# Sheet1.net
KiCad netlist of a schematic drawn in Altium Designer
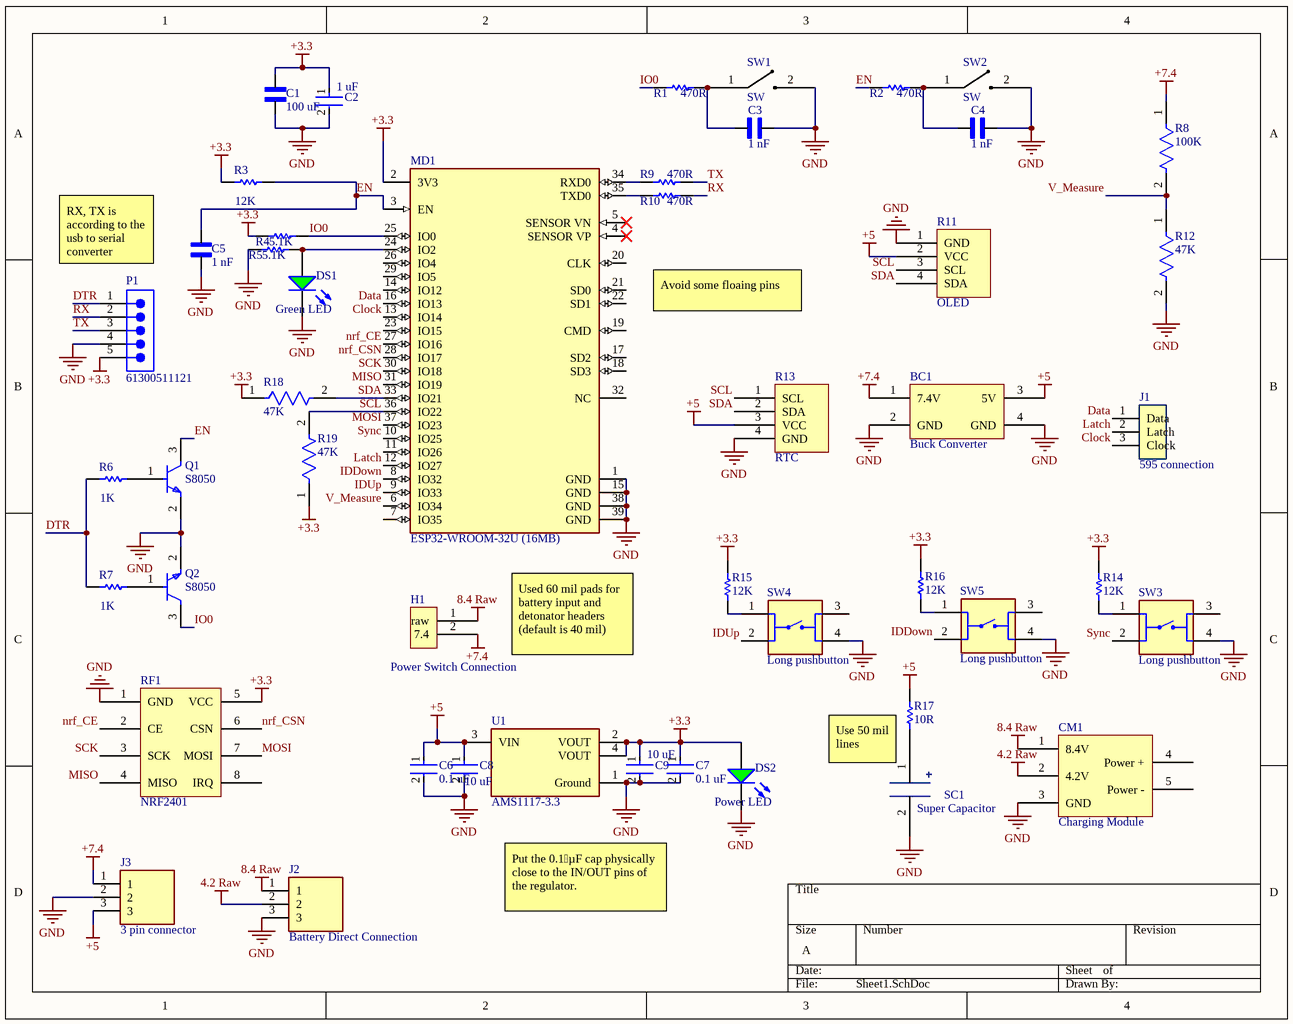
[diagram p0: Sheet1.SchDoc]

(export (version "E")
  (design (tool "Eeschema 10.0.6"))
  (components
    (comp (ref "BC1")
      (value "Buck Converter")
      (footprint "Buck Converter")
      (libsource (lib "Firework Detenator PCB") (part "Buck Converter"))
    )
    (comp (ref "C1")
      (value "100 uF")
      (footprint "0805 CAP")
      (description "10000 pF Â±5% 16V Ceramic Capacitor X7R 0805 (2012 Metric)")
      (fields (field (name "MF") "AVX") (field (name "MP") "0805YC103J4T2A"))
      (libsource (lib "Firework Detenator PCB") (part "0805 cap"))
    )
    (comp (ref "C2")
      (value "1 uF")
      (footprint "FP-CL21-IPC_A")
      (description "CL21 Series 0805 10uF 25V ±10% Tolerance X5R Multilayer Ceramic Chip Capacitor")
      (fields (field (name "TOLERANCE") "10%"))
      (libsource (lib "Altium Content Vault") (part "b4654b650e69147ec39a6b967a45e02"))
    )
    (comp (ref "C3")
      (value "1 nF")
      (footprint "0805 CAP")
      (description "10000 pF Â±5% 16V Ceramic Capacitor X7R 0805 (2012 Metric)")
      (fields (field (name "MF") "AVX") (field (name "MP") "0805YC103J4T2A"))
      (libsource (lib "") (part "0805 cap_1"))
    )
    (comp (ref "C4")
      (value "1 nF")
      (footprint "0805 CAP")
      (description "10000 pF Â±5% 16V Ceramic Capacitor X7R 0805 (2012 Metric)")
      (fields (field (name "MF") "AVX") (field (name "MP") "0805YC103J4T2A"))
      (libsource (lib "") (part "0805 cap_1"))
    )
    (comp (ref "C5")
      (value "1 nF")
      (footprint "0805 CAP")
      (description "10000 pF Â±5% 16V Ceramic Capacitor X7R 0805 (2012 Metric)")
      (fields (field (name "MF") "AVX") (field (name "MP") "0805YC103J4T2A"))
      (libsource (lib "Firework Detenator PCB") (part "0805 cap"))
    )
    (comp (ref "C6")
      (value "0.1 uF")
      (footprint "FP-CC0805-0_85-MFG")
      (description "CAP CER 0.1UF 50V X7R 0805")
      (fields (field (name "TOLERANCE") "0.1") (field (name "MANUFACTURER PART NUMBER") "CC0805KRX7R9BB104"))
      (libsource (lib "Altium Content Vault") (part "11868f565c42a9108669ba33697ecf6"))
    )
    (comp (ref "C7")
      (value "0.1 uF")
      (footprint "FP-CC0805-0_85-MFG")
      (description "CAP CER 0.1UF 50V X7R 0805")
      (fields (field (name "TOLERANCE") "0.1") (field (name "MANUFACTURER PART NUMBER") "CC0805KRX7R9BB104"))
      (libsource (lib "Altium Content Vault") (part "11868f565c42a9108669ba33697ecf6"))
    )
    (comp (ref "C8")
      (value "10 uF")
      (footprint "FP-CL21-IPC_A")
      (description "CL21 Series 0805 10uF 25V ±10% Tolerance X5R Multilayer Ceramic Chip Capacitor")
      (fields (field (name "TOLERANCE") "10%"))
      (libsource (lib "Altium Content Vault") (part "b4654b650e69147ec39a6b967a45e02"))
    )
    (comp (ref "C9")
      (value "10 uF")
      (footprint "FP-CL21-IPC_A")
      (description "CL21 Series 0805 10uF 25V ±10% Tolerance X5R Multilayer Ceramic Chip Capacitor")
      (fields (field (name "TOLERANCE") "10%"))
      (libsource (lib "Altium Content Vault") (part "b4654b650e69147ec39a6b967a45e02"))
    )
    (comp (ref "CM1")
      (value "Charging Module")
      (footprint "2S Charging Module")
      (libsource (lib "Firework Detenator PCB") (part "2S Charging module"))
    )
    (comp (ref "DS1")
      (value "Green LED")
      (footprint "DIAL-0805-2_V")
      (description "Single Color, 2 V, -30 to 85 degC, 2-Pin SMD (0805), RoHS, Tape and Reel")
      (fields (field (name "MANUFACTURER") "Dialight"))
      (libsource (lib "Altium Content Vault") (part "LED-GREEN-AK-2"))
    )
    (comp (ref "DS2")
      (value "Power LED")
      (footprint "DIAL-0805-2_V")
      (description "Single Color, 2 V, -30 to 85 degC, 2-Pin SMD (0805), RoHS, Tape and Reel")
      (fields (field (name "MANUFACTURER") "Dialight"))
      (libsource (lib "Altium Content Vault") (part "LED-GREEN-AK-2"))
    )
    (comp (ref "H1")
      (value "Power Switch Connection")
      (footprint "2 Pin Header L")
      (libsource (lib "Firework Detenator PCB") (part "2 pin header"))
    )
    (comp (ref "J1")
      (value "595 connection")
      (footprint "3 pin header")
      (description "3P,STRAIGHT,SIDE ENTRY,3.5MM")
      (fields (field (name "MF") "TE Connectivity") (field (name "MP") "1546551-3"))
      (libsource (lib "Firework Detenator PCB") (part "3 pin header"))
    )
    (comp (ref "J2")
      (value "Battery Direct Connection")
      (footprint "3 pin connector")
      (description "3P,STRAIGHT,SIDE ENTRY,3.5MM")
      (fields (field (name "MF") "TE Connectivity") (field (name "MP") "1546551-3"))
      (libsource (lib "Firework Detenator PCB") (part "3 pin connector"))
    )
    (comp (ref "J3")
      (value "3 pin connector")
      (footprint "3 pin connector")
      (description "3P,STRAIGHT,SIDE ENTRY,3.5MM")
      (fields (field (name "MF") "TE Connectivity") (field (name "MP") "1546551-3"))
      (libsource (lib "Firework Detenator PCB") (part "3 pin connector"))
    )
    (comp (ref "MD1")
      (value "ESP32-WROOM-32U (16MB)")
      (footprint "FP-ESP32-WROOM-32U_16MB-MFG")
      (description "RX TXRX MODULE WIFI U.FL SMD")
      (libsource (lib "Altium Content Vault") (part "9bfa6d67090bf770919afa182987e90"))
    )
    (comp (ref "P1")
      (value "61300511121")
      (footprint "61300511121")
      (libsource (lib "Altium Content Vault") (part "Header_Male_1R_05P"))
    )
    (comp (ref "Q1")
      (value "S8050")
      (footprint "FP-SOT23-IPC_A")
      (description "TRANS NPN 40V 0.2A SMD SOT23-3")
      (libsource (lib "Altium Content Vault") (part "b44e953556f554d0102664c7d152cb4"))
    )
    (comp (ref "Q2")
      (value "S8050")
      (footprint "FP-SOT23-IPC_A")
      (description "TRANS NPN 40V 0.2A SMD SOT23-3")
      (libsource (lib "Altium Content Vault") (part "b44e953556f554d0102664c7d152cb4"))
    )
    (comp (ref "R1")
      (value "470R")
      (footprint "RESC2013X50X30LL20T20")
      (fields (field (name "MANUFACTURER") "Vishay Dale") (field (name "PART NUMBER") "CRCW08050000Z0EA"))
      (libsource (lib "Altium Content Vault") (part "RES"))
    )
    (comp (ref "R2")
      (value "470R")
      (footprint "RESC2013X50X30LL20T20")
      (fields (field (name "MANUFACTURER") "Vishay Dale") (field (name "PART NUMBER") "CRCW08050000Z0EA"))
      (libsource (lib "Altium Content Vault") (part "RES"))
    )
    (comp (ref "R3")
      (value "12K")
      (footprint "RESC2013X50X30LL20T20")
      (fields (field (name "MANUFACTURER") "Vishay Dale") (field (name "PART NUMBER") "CRCW08050000Z0EA"))
      (libsource (lib "Altium Content Vault") (part "RES"))
    )
    (comp (ref "R4")
      (value "5.1K")
      (footprint "RESC2013X50X30LL20T20")
      (fields (field (name "MANUFACTURER") "Vishay Dale") (field (name "PART NUMBER") "CRCW08050000Z0EA"))
      (libsource (lib "Altium Content Vault") (part "RES"))
    )
    (comp (ref "R5")
      (value "5.1K")
      (footprint "RESC2013X50X30LL20T20")
      (fields (field (name "MANUFACTURER") "Vishay Dale") (field (name "PART NUMBER") "CRCW08050000Z0EA"))
      (libsource (lib "Altium Content Vault") (part "RES"))
    )
    (comp (ref "R6")
      (value "1K")
      (footprint "RESC2013X50X30LL20T20")
      (fields (field (name "MANUFACTURER") "Vishay Dale") (field (name "PART NUMBER") "CRCW08050000Z0EA"))
      (libsource (lib "Altium Content Vault") (part "RES"))
    )
    (comp (ref "R7")
      (value "1K")
      (footprint "RESC2013X50X30LL20T20")
      (fields (field (name "MANUFACTURER") "Vishay Dale") (field (name "PART NUMBER") "CRCW08050000Z0EA"))
      (libsource (lib "Altium Content Vault") (part "RES"))
    )
    (comp (ref "R8")
      (value "100K")
      (footprint "FP-RC0805-0_6-MFG")
      (description "RES SMD 100K OHM 5% 1/8W 0805")
      (fields (field (name "TOLERANCE") "5%"))
      (libsource (lib "Altium Content Vault") (part "8db39607336c341a927600551d01821"))
    )
    (comp (ref "R9")
      (value "470R")
      (footprint "RESC2013X50X30LL20T20")
      (fields (field (name "MANUFACTURER") "Vishay Dale") (field (name "PART NUMBER") "CRCW08050000Z0EA"))
      (libsource (lib "Altium Content Vault") (part "RES"))
    )
    (comp (ref "R10")
      (value "470R")
      (footprint "RESC2013X50X30LL20T20")
      (fields (field (name "MANUFACTURER") "Vishay Dale") (field (name "PART NUMBER") "CRCW08050000Z0EA"))
      (libsource (lib "Altium Content Vault") (part "RES"))
    )
    (comp (ref "R11")
      (value "OLED")
      (footprint "OLED")
      (libsource (lib "Firework Detenator PCB") (part "OLED"))
    )
    (comp (ref "R12")
      (value "47K")
      (footprint "FP-CRCW0805-e3-MFG")
      (description "RES Thick Film, 47kΩ, 1%, 0.125W, 100ppm/°C, 0805")
      (fields (field (name "TOLERANCE") "1%"))
      (libsource (lib "Altium Content Vault") (part "1029c3af85768c4190bb7ad29bc67b5"))
    )
    (comp (ref "R13") (value "RTC") (footprint "RTC") (libsource (lib "Firework Detenator PCB") (part "RTC")))
    (comp (ref "R14")
      (value "12K")
      (footprint "RESC2013X50X30LL20T20")
      (fields (field (name "MANUFACTURER") "Vishay Dale") (field (name "PART NUMBER") "CRCW08050000Z0EA"))
      (libsource (lib "Altium Content Vault") (part "RES"))
    )
    (comp (ref "R15")
      (value "12K")
      (footprint "RESC2013X50X30LL20T20")
      (fields (field (name "MANUFACTURER") "Vishay Dale") (field (name "PART NUMBER") "CRCW08050000Z0EA"))
      (libsource (lib "Altium Content Vault") (part "RES"))
    )
    (comp (ref "R16")
      (value "12K")
      (footprint "RESC2013X50X30LL20T20")
      (fields (field (name "MANUFACTURER") "Vishay Dale") (field (name "PART NUMBER") "CRCW08050000Z0EA"))
      (libsource (lib "Altium Content Vault") (part "RES"))
    )
    (comp (ref "R17")
      (value "10R")
      (footprint "RESC2013X50X30LL20T20")
      (fields (field (name "MANUFACTURER") "Vishay Dale") (field (name "PART NUMBER") "CRCW08050000Z0EA"))
      (libsource (lib "Altium Content Vault") (part "RES"))
    )
    (comp (ref "R18")
      (value "47K")
      (footprint "FP-CRCW0805-e3-MFG")
      (description "RES Thick Film, 47kΩ, 1%, 0.125W, 100ppm/°C, 0805")
      (fields (field (name "TOLERANCE") "1%"))
      (libsource (lib "Altium Content Vault") (part "1029c3af85768c4190bb7ad29bc67b5"))
    )
    (comp (ref "R19")
      (value "47K")
      (footprint "FP-CRCW0805-e3-MFG")
      (description "RES Thick Film, 47kΩ, 1%, 0.125W, 100ppm/°C, 0805")
      (fields (field (name "TOLERANCE") "1%"))
      (libsource (lib "Altium Content Vault") (part "1029c3af85768c4190bb7ad29bc67b5"))
    )
    (comp (ref "RF1")
      (value "NRF2401")
      (footprint "nrf2401")
      (libsource (lib "Firework Detenator PCB") (part "nrf2401"))
    )
    (comp (ref "SC1")
      (value "Super Capacitor")
      (footprint "Super Capacitor")
      (libsource (lib "Firework Detenator PCB") (part "Super Capacitor"))
    )
    (comp (ref "SW1")
      (value "SW")
      (footprint "smd push button 2")
      (libsource (lib "Firework Detenator PCB") (part "push button smd"))
    )
    (comp (ref "SW2")
      (value "SW")
      (footprint "smd push button 2")
      (libsource (lib "Firework Detenator PCB") (part "push button smd"))
    )
    (comp (ref "SW3")
      (value "Long pushbutton")
      (footprint "TH PB")
      (description "Switch Push Button OFF (ON) SPST Round Button 0.05A 24VDC Momentary Contact PC Pins Thru-Hole")
      (fields (field (name "MP") "1825910-6") (field (name "MF") "TE Connectivity"))
      (libsource (lib "Firework Detenator PCB") (part "TH PB"))
    )
    (comp (ref "SW4")
      (value "Long pushbutton")
      (footprint "TH PB")
      (description "Switch Push Button OFF (ON) SPST Round Button 0.05A 24VDC Momentary Contact PC Pins Thru-Hole")
      (fields (field (name "MP") "1825910-6") (field (name "MF") "TE Connectivity"))
      (libsource (lib "Firework Detenator PCB") (part "TH PB"))
    )
    (comp (ref "SW5")
      (value "Long pushbutton")
      (footprint "TH PB")
      (description "Switch Push Button OFF (ON) SPST Round Button 0.05A 24VDC Momentary Contact PC Pins Thru-Hole")
      (fields (field (name "MP") "1825910-6") (field (name "MF") "TE Connectivity"))
      (libsource (lib "Firework Detenator PCB") (part "TH PB"))
    )
    (comp (ref "U1")
      (value "AMS1117-3.3")
      (footprint "FP-AMS1117-IPC_C")
      (description "LDO Voltage Regulators 1A, 3.3V")
      (fields
        (field (name "OCTOPART") "https://octopart.com/ams1117-3.3-advanced+monolithic+systems-25899300")
        (field (name "MANUFACTURER") "Advanced Monolithic Systems")
      )
      (libsource (lib "Altium Content Vault") (part "8bdbb5f8e77002000e30dd2845d0354"))
    )
  )
  (nets
    (net (code "1") (name "+3.3") (class "Default")
      (node (ref "C1") (pin "2") (pinfunction "2_2") (pintype "passive"))
      (node (ref "C2") (pin "1") (pinfunction "1_1") (pintype "passive"))
      (node (ref "C7") (pin "1") (pinfunction "1_1") (pintype "passive"))
      (node (ref "C9") (pin "1") (pinfunction "1_1") (pintype "passive"))
      (node (ref "DS2") (pin "1") (pinfunction "A_1") (pintype "passive"))
      (node (ref "MD1") (pin "2") (pinfunction "3V3_2") (pintype "power_in"))
      (node (ref "P1") (pin "5") (pinfunction "5_5") (pintype "passive"))
      (node (ref "R14") (pin "2") (pinfunction "2_2") (pintype "passive"))
      (node (ref "R15") (pin "2") (pinfunction "2_2") (pintype "passive"))
      (node (ref "R16") (pin "2") (pinfunction "2_2") (pintype "passive"))
      (node (ref "R18") (pin "1") (pinfunction "1_1") (pintype "passive"))
      (node (ref "R19") (pin "1") (pinfunction "1_1") (pintype "passive"))
      (node (ref "R3") (pin "1") (pinfunction "1_1") (pintype "passive"))
      (node (ref "R4") (pin "1") (pinfunction "1_1") (pintype "passive"))
      (node (ref "RF1") (pin "5") (pinfunction "VCC_5") (pintype "passive"))
      (node (ref "U1") (pin "2") (pinfunction "VOUT_2") (pintype "passive"))
      (node (ref "U1") (pin "4") (pinfunction "VOUT_4") (pintype "passive"))
    )
    (net (code "2") (name "+5") (class "Default")
      (node (ref "BC1") (pin "3") (pinfunction "5V_3") (pintype "passive"))
      (node (ref "C6") (pin "1") (pinfunction "1_1") (pintype "passive"))
      (node (ref "C8") (pin "1") (pinfunction "1_1") (pintype "passive"))
      (node (ref "J3") (pin "3") (pinfunction "3_3") (pintype "passive"))
      (node (ref "R11") (pin "2") (pinfunction "VCC_2") (pintype "passive"))
      (node (ref "R13") (pin "3") (pinfunction "VCC_3") (pintype "passive"))
      (node (ref "R17") (pin "2") (pinfunction "2_2") (pintype "passive"))
      (node (ref "U1") (pin "3") (pinfunction "VIN_3") (pintype "power_in"))
    )
    (net (code "3") (name "+7.4") (class "Default")
      (node (ref "BC1") (pin "1") (pinfunction "7.4V_1") (pintype "passive"))
      (node (ref "H1") (pin "2") (pinfunction "7.4_2") (pintype "passive"))
      (node (ref "J3") (pin "1") (pinfunction "1_1") (pintype "passive"))
      (node (ref "R8") (pin "1") (pinfunction "1_1") (pintype "passive"))
    )
    (net (code "4") (name "/Clock") (class "Default")
      (node (ref "J1") (pin "3") (pinfunction "Clock_3") (pintype "passive"))
      (node (ref "MD1") (pin "13") (pinfunction "IO14_13") (pintype "bidirectional"))
    )
    (net (code "5") (name "/DTR") (class "Default")
      (node (ref "P1") (pin "1") (pinfunction "1_1") (pintype "passive"))
      (node (ref "R6") (pin "1") (pinfunction "1_1") (pintype "passive"))
      (node (ref "R7") (pin "1") (pinfunction "1_1") (pintype "passive"))
    )
    (net (code "6") (name "/Data") (class "Default")
      (node (ref "J1") (pin "1") (pinfunction "Data_1") (pintype "passive"))
      (node (ref "MD1") (pin "16") (pinfunction "IO13_16") (pintype "bidirectional"))
    )
    (net (code "7") (name "/EN") (class "Default")
      (node (ref "C5") (pin "2") (pinfunction "2_2") (pintype "passive"))
      (node (ref "MD1") (pin "3") (pinfunction "EN_3") (pintype "input"))
      (node (ref "Q1") (pin "3") (pinfunction "C_3") (pintype "passive"))
      (node (ref "R2") (pin "1") (pinfunction "1_1") (pintype "passive"))
      (node (ref "R3") (pin "2") (pinfunction "2_2") (pintype "passive"))
    )
    (net (code "8") (name "/IDDown") (class "Default")
      (node (ref "MD1") (pin "8") (pinfunction "IO32_8") (pintype "bidirectional"))
      (node (ref "SW5") (pin "2") (pinfunction "2_2") (pintype "passive"))
    )
    (net (code "9") (name "/IDUp") (class "Default")
      (node (ref "MD1") (pin "9") (pinfunction "IO33_9") (pintype "bidirectional"))
      (node (ref "SW4") (pin "2") (pinfunction "2_2") (pintype "passive"))
    )
    (net (code "10") (name "/IO0") (class "Default")
      (node (ref "MD1") (pin "25") (pinfunction "IO0_25") (pintype "bidirectional"))
      (node (ref "Q2") (pin "3") (pinfunction "C_3") (pintype "passive"))
      (node (ref "R1") (pin "1") (pinfunction "1_1") (pintype "passive"))
      (node (ref "R4") (pin "2") (pinfunction "2_2") (pintype "passive"))
    )
    (net (code "11") (name "/Latch") (class "Default")
      (node (ref "J1") (pin "2") (pinfunction "Latch_2") (pintype "passive"))
      (node (ref "MD1") (pin "12") (pinfunction "IO27_12") (pintype "bidirectional"))
    )
    (net (code "12") (name "/MISO") (class "Default")
      (node (ref "MD1") (pin "31") (pinfunction "IO19_31") (pintype "bidirectional"))
      (node (ref "RF1") (pin "4") (pinfunction "MISO_4") (pintype "passive"))
    )
    (net (code "13") (name "/MOSI") (class "Default")
      (node (ref "MD1") (pin "37") (pinfunction "IO23_37") (pintype "bidirectional"))
      (node (ref "RF1") (pin "7") (pinfunction "MOSI_7") (pintype "passive"))
    )
    (net (code "14") (name "/RX") (class "Default")
      (node (ref "P1") (pin "2") (pinfunction "2_2") (pintype "passive"))
      (node (ref "R10") (pin "2") (pinfunction "2_2") (pintype "passive"))
    )
    (net (code "15") (name "/SCK") (class "Default")
      (node (ref "MD1") (pin "30") (pinfunction "IO18_30") (pintype "bidirectional"))
      (node (ref "RF1") (pin "3") (pinfunction "SCK_3") (pintype "passive"))
    )
    (net (code "16") (name "/SCL") (class "Default")
      (node (ref "MD1") (pin "36") (pinfunction "IO22_36") (pintype "bidirectional"))
      (node (ref "R11") (pin "3") (pinfunction "SCL_3") (pintype "passive"))
      (node (ref "R13") (pin "1") (pinfunction "SCL_1") (pintype "passive"))
      (node (ref "R19") (pin "2") (pinfunction "2_2") (pintype "passive"))
    )
    (net (code "17") (name "/SDA") (class "Default")
      (node (ref "MD1") (pin "33") (pinfunction "IO21_33") (pintype "bidirectional"))
      (node (ref "R11") (pin "4") (pinfunction "SDA_4") (pintype "passive"))
      (node (ref "R13") (pin "2") (pinfunction "SDA_2") (pintype "passive"))
      (node (ref "R18") (pin "2") (pinfunction "2_2") (pintype "passive"))
    )
    (net (code "18") (name "/Sync") (class "Default")
      (node (ref "MD1") (pin "10") (pinfunction "IO25_10") (pintype "bidirectional"))
      (node (ref "SW3") (pin "2") (pinfunction "2_2") (pintype "passive"))
    )
    (net (code "19") (name "/TX") (class "Default")
      (node (ref "P1") (pin "3") (pinfunction "3_3") (pintype "passive"))
      (node (ref "R9") (pin "2") (pinfunction "2_2") (pintype "passive"))
    )
    (net (code "20") (name "/V_Measure") (class "Default")
      (node (ref "MD1") (pin "6") (pinfunction "IO34_6") (pintype "bidirectional"))
      (node (ref "R12") (pin "1") (pinfunction "1_1") (pintype "passive"))
      (node (ref "R8") (pin "2") (pinfunction "2_2") (pintype "passive"))
    )
    (net (code "21") (name "/nrf_CE") (class "Default")
      (node (ref "MD1") (pin "27") (pinfunction "IO16_27") (pintype "bidirectional"))
      (node (ref "RF1") (pin "2") (pinfunction "CE_2") (pintype "passive"))
    )
    (net (code "22") (name "/nrf_CSN") (class "Default")
      (node (ref "MD1") (pin "28") (pinfunction "IO17_28") (pintype "bidirectional"))
      (node (ref "RF1") (pin "6") (pinfunction "CSN_6") (pintype "passive"))
    )
    (net (code "23") (name "4.2 Raw") (class "Default")
      (node (ref "CM1") (pin "2") (pinfunction "4.2V_2") (pintype "passive"))
      (node (ref "J2") (pin "2") (pinfunction "2_2") (pintype "passive"))
    )
    (net (code "24") (name "8.4 Raw") (class "Default")
      (node (ref "CM1") (pin "1") (pinfunction "8.4V_1") (pintype "passive"))
      (node (ref "H1") (pin "1") (pinfunction "raw_1") (pintype "passive"))
      (node (ref "J2") (pin "1") (pinfunction "1_1") (pintype "passive"))
    )
    (net (code "25") (name "GND") (class "Default")
      (node (ref "BC1") (pin "2") (pinfunction "GND_2") (pintype "passive"))
      (node (ref "BC1") (pin "4") (pinfunction "GND_4") (pintype "passive"))
      (node (ref "C1") (pin "1") (pinfunction "1_1") (pintype "passive"))
      (node (ref "C2") (pin "2") (pinfunction "2_2") (pintype "passive"))
      (node (ref "C3") (pin "1") (pinfunction "1_1") (pintype "passive"))
      (node (ref "C4") (pin "1") (pinfunction "1_1") (pintype "passive"))
      (node (ref "C5") (pin "1") (pinfunction "1_1") (pintype "passive"))
      (node (ref "C6") (pin "2") (pinfunction "2_2") (pintype "passive"))
      (node (ref "C7") (pin "2") (pinfunction "2_2") (pintype "passive"))
      (node (ref "C8") (pin "2") (pinfunction "2_2") (pintype "passive"))
      (node (ref "C9") (pin "2") (pinfunction "2_2") (pintype "passive"))
      (node (ref "CM1") (pin "3") (pinfunction "GND_3") (pintype "passive"))
      (node (ref "DS1") (pin "2") (pinfunction "K_2") (pintype "passive"))
      (node (ref "DS2") (pin "2") (pinfunction "K_2") (pintype "passive"))
      (node (ref "J2") (pin "3") (pinfunction "3_3") (pintype "passive"))
      (node (ref "J3") (pin "2") (pinfunction "2_2") (pintype "passive"))
      (node (ref "MD1") (pin "1") (pinfunction "GND_1") (pintype "power_in"))
      (node (ref "MD1") (pin "15") (pinfunction "GND_15") (pintype "power_in"))
      (node (ref "MD1") (pin "38") (pinfunction "GND_38") (pintype "power_in"))
      (node (ref "MD1") (pin "39") (pinfunction "GND_39") (pintype "power_in"))
      (node (ref "P1") (pin "4") (pinfunction "4_4") (pintype "passive"))
      (node (ref "Q1") (pin "2") (pinfunction "E_2") (pintype "passive"))
      (node (ref "Q2") (pin "2") (pinfunction "E_2") (pintype "passive"))
      (node (ref "R11") (pin "1") (pinfunction "GND_1") (pintype "passive"))
      (node (ref "R12") (pin "2") (pinfunction "2_2") (pintype "passive"))
      (node (ref "R13") (pin "4") (pinfunction "GND_4") (pintype "passive"))
      (node (ref "R5") (pin "1") (pinfunction "1_1") (pintype "passive"))
      (node (ref "RF1") (pin "1") (pinfunction "GND_1") (pintype "passive"))
      (node (ref "SC1") (pin "2") (pinfunction "2_2") (pintype "passive"))
      (node (ref "SW1") (pin "2") (pinfunction "2_2") (pintype "passive"))
      (node (ref "SW2") (pin "2") (pinfunction "2_2") (pintype "passive"))
      (node (ref "SW3") (pin "4") (pinfunction "4_4") (pintype "passive"))
      (node (ref "SW4") (pin "4") (pinfunction "4_4") (pintype "passive"))
      (node (ref "SW5") (pin "4") (pinfunction "4_4") (pintype "passive"))
      (node (ref "U1") (pin "1") (pinfunction "Ground_1") (pintype "power_in"))
    )
    (net (code "26") (name "Net-(C3-Pad2)") (class "Default")
      (node (ref "C3") (pin "2") (pinfunction "2_2") (pintype "passive"))
      (node (ref "R1") (pin "2") (pinfunction "2_2") (pintype "passive"))
      (node (ref "SW1") (pin "1") (pinfunction "1_1") (pintype "passive"))
    )
    (net (code "27") (name "Net-(C4-Pad2)") (class "Default")
      (node (ref "C4") (pin "2") (pinfunction "2_2") (pintype "passive"))
      (node (ref "R2") (pin "2") (pinfunction "2_2") (pintype "passive"))
      (node (ref "SW2") (pin "1") (pinfunction "1_1") (pintype "passive"))
    )
    (net (code "28") (name "Net-(DS1-A)") (class "Default")
      (node (ref "DS1") (pin "1") (pinfunction "A_1") (pintype "passive"))
      (node (ref "MD1") (pin "24") (pinfunction "IO2_24") (pintype "bidirectional"))
      (node (ref "R5") (pin "2") (pinfunction "2_2") (pintype "passive"))
    )
    (net (code "29") (name "Net-(MD1-RXD0)") (class "Default")
      (node (ref "MD1") (pin "34") (pinfunction "RXD0_34") (pintype "bidirectional"))
      (node (ref "R9") (pin "1") (pinfunction "1_1") (pintype "passive"))
    )
    (net (code "30") (name "Net-(MD1-TXD0)") (class "Default")
      (node (ref "MD1") (pin "35") (pinfunction "TXD0_35") (pintype "bidirectional"))
      (node (ref "R10") (pin "1") (pinfunction "1_1") (pintype "passive"))
    )
    (net (code "31") (name "Net-(Q1-B)") (class "Default")
      (node (ref "Q1") (pin "1") (pinfunction "B_1") (pintype "passive"))
      (node (ref "R6") (pin "2") (pinfunction "2_2") (pintype "passive"))
    )
    (net (code "32") (name "Net-(Q2-B)") (class "Default")
      (node (ref "Q2") (pin "1") (pinfunction "B_1") (pintype "passive"))
      (node (ref "R7") (pin "2") (pinfunction "2_2") (pintype "passive"))
    )
    (net (code "33") (name "Net-(R14-Pad1)") (class "Default")
      (node (ref "R14") (pin "1") (pinfunction "1_1") (pintype "passive"))
      (node (ref "SW3") (pin "1") (pinfunction "1_1") (pintype "passive"))
    )
    (net (code "34") (name "Net-(R15-Pad1)") (class "Default")
      (node (ref "R15") (pin "1") (pinfunction "1_1") (pintype "passive"))
      (node (ref "SW4") (pin "1") (pinfunction "1_1") (pintype "passive"))
    )
    (net (code "35") (name "Net-(R16-Pad1)") (class "Default")
      (node (ref "R16") (pin "1") (pinfunction "1_1") (pintype "passive"))
      (node (ref "SW5") (pin "1") (pinfunction "1_1") (pintype "passive"))
    )
    (net (code "36") (name "Net-(R17-Pad1)") (class "Default")
      (node (ref "R17") (pin "1") (pinfunction "1_1") (pintype "passive"))
      (node (ref "SC1") (pin "1") (pinfunction "1_1") (pintype "passive"))
    )
    (net (code "37") (name "unconnected-(CM1-Power_+-Pad4)") (class "Default")
      (node (ref "CM1") (pin "4") (pinfunction "Power_+_4") (pintype "passive"))
    )
    (net (code "38") (name "unconnected-(CM1-Power_--Pad5)") (class "Default")
      (node (ref "CM1") (pin "5") (pinfunction "Power_-_5") (pintype "passive"))
    )
    (net (code "39") (name "unconnected-(MD1-CLK-Pad20)") (class "Default")
      (node (ref "MD1") (pin "20") (pinfunction "CLK_20") (pintype "bidirectional"))
    )
    (net (code "40") (name "unconnected-(MD1-CMD-Pad19)") (class "Default")
      (node (ref "MD1") (pin "19") (pinfunction "CMD_19") (pintype "bidirectional"))
    )
    (net (code "41") (name "unconnected-(MD1-IO4-Pad26)") (class "Default")
      (node (ref "MD1") (pin "26") (pinfunction "IO4_26") (pintype "bidirectional"))
    )
    (net (code "42") (name "unconnected-(MD1-IO5-Pad29)") (class "Default")
      (node (ref "MD1") (pin "29") (pinfunction "IO5_29") (pintype "bidirectional"))
    )
    (net (code "43") (name "unconnected-(MD1-IO12-Pad14)") (class "Default")
      (node (ref "MD1") (pin "14") (pinfunction "IO12_14") (pintype "bidirectional"))
    )
    (net (code "44") (name "unconnected-(MD1-IO15-Pad23)") (class "Default")
      (node (ref "MD1") (pin "23") (pinfunction "IO15_23") (pintype "bidirectional"))
    )
    (net (code "45") (name "unconnected-(MD1-IO26-Pad11)") (class "Default")
      (node (ref "MD1") (pin "11") (pinfunction "IO26_11") (pintype "bidirectional"))
    )
    (net (code "46") (name "unconnected-(MD1-IO35-Pad7)") (class "Default")
      (node (ref "MD1") (pin "7") (pinfunction "IO35_7") (pintype "bidirectional"))
    )
    (net (code "47") (name "unconnected-(MD1-NC-Pad32)") (class "Default")
      (node (ref "MD1") (pin "32") (pinfunction "NC_32") (pintype "passive"))
    )
    (net (code "48") (name "unconnected-(MD1-SD0-Pad21)") (class "Default")
      (node (ref "MD1") (pin "21") (pinfunction "SD0_21") (pintype "bidirectional"))
    )
    (net (code "49") (name "unconnected-(MD1-SD1-Pad22)") (class "Default")
      (node (ref "MD1") (pin "22") (pinfunction "SD1_22") (pintype "bidirectional"))
    )
    (net (code "50") (name "unconnected-(MD1-SD2-Pad17)") (class "Default")
      (node (ref "MD1") (pin "17") (pinfunction "SD2_17") (pintype "bidirectional"))
    )
    (net (code "51") (name "unconnected-(MD1-SD3-Pad18)") (class "Default")
      (node (ref "MD1") (pin "18") (pinfunction "SD3_18") (pintype "bidirectional"))
    )
    (net (code "52") (name "unconnected-(MD1-SENSOR_VN-Pad5)") (class "Default")
      (node (ref "MD1") (pin "5") (pinfunction "SENSOR_VN_5") (pintype "input+no_connect"))
    )
    (net (code "53") (name "unconnected-(MD1-SENSOR_VP-Pad4)") (class "Default")
      (node (ref "MD1") (pin "4") (pinfunction "SENSOR_VP_4") (pintype "input+no_connect"))
    )
    (net (code "54") (name "unconnected-(RF1-IRQ-Pad8)") (class "Default")
      (node (ref "RF1") (pin "8") (pinfunction "IRQ_8") (pintype "passive"))
    )
    (net (code "55") (name "unconnected-(SW3-Pad3)") (class "Default")
      (node (ref "SW3") (pin "3") (pinfunction "3_3") (pintype "passive"))
    )
    (net (code "56") (name "unconnected-(SW4-Pad3)") (class "Default")
      (node (ref "SW4") (pin "3") (pinfunction "3_3") (pintype "passive"))
    )
    (net (code "57") (name "unconnected-(SW5-Pad3)") (class "Default")
      (node (ref "SW5") (pin "3") (pinfunction "3_3") (pintype "passive"))
    )
  )
)
